# LED_Triangle.net
KiCad netlist of a schematic drawn in EAGLE
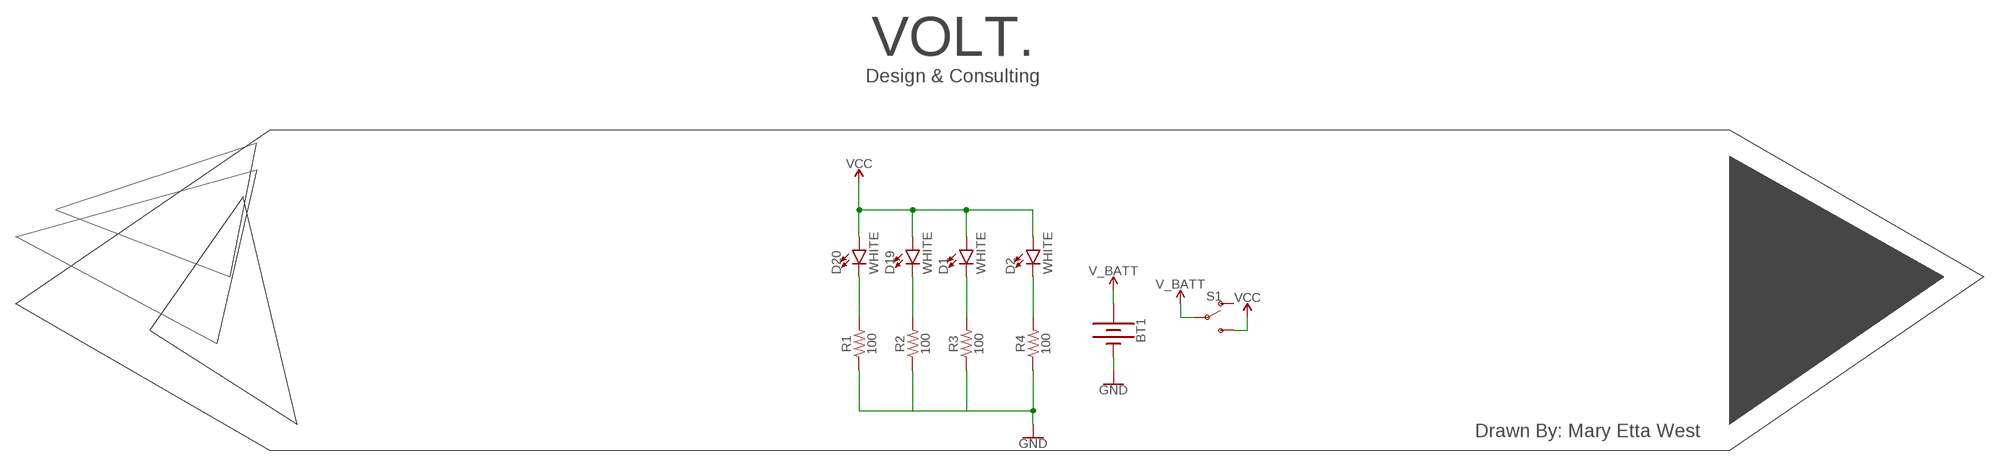
[diagram p0: schematic, sheet 1]

(export (version "E")
  (design (tool "Eeschema 10.0.6"))
  (components
    (comp (ref "BT1")
      (value "BATTERY-12MM_SMD")
      (footprint "eagle-import:BATTCON_12MM")
      (libsource (lib "eagle-import") (part "BATTERY-12MM_SMD"))
    )
    (comp (ref "D1")
      (value "WHITE")
      (footprint "eagle-import:LED-1206")
      (libsource (lib "eagle-import") (part "LED-WHITE1206"))
    )
    (comp (ref "D2")
      (value "WHITE")
      (footprint "eagle-import:LED-1206")
      (libsource (lib "eagle-import") (part "LED-WHITE1206"))
    )
    (comp (ref "D19")
      (value "WHITE")
      (footprint "eagle-import:LED-1206")
      (libsource (lib "eagle-import") (part "LED-WHITE1206"))
    )
    (comp (ref "D20")
      (value "WHITE")
      (footprint "eagle-import:LED-1206")
      (libsource (lib "eagle-import") (part "LED-WHITE1206"))
    )
    (comp (ref "R1")
      (value "100")
      (footprint "eagle-import:0603")
      (libsource (lib "eagle-import") (part "100OHM-0603-1/4W-5%"))
    )
    (comp (ref "R2")
      (value "100")
      (footprint "eagle-import:0603")
      (libsource (lib "eagle-import") (part "100OHM-0603-1/4W-5%"))
    )
    (comp (ref "R3")
      (value "100")
      (footprint "eagle-import:0603")
      (libsource (lib "eagle-import") (part "100OHM-0603-1/4W-5%"))
    )
    (comp (ref "R4")
      (value "100")
      (footprint "eagle-import:0603")
      (libsource (lib "eagle-import") (part "100OHM-0603-1/4W-5%"))
    )
    (comp (ref "S1")
      (value "SWITCH-SPDT-SMD-RIGHT-ANGLE")
      (footprint "eagle-import:SWITCH_SPST_SMD_A")
      (libsource (lib "eagle-import") (part "SWITCH-SPDT-SMD-RIGHT-ANGLE"))
    )
  )
  (nets
    (net (code "1") (name "GND") (class "Default")
      (node (ref "BT1") (pin "GND") (pinfunction "-_GND") (pintype "power_in"))
      (node (ref "R1") (pin "1") (pinfunction "1_1") (pintype "passive"))
      (node (ref "R2") (pin "1") (pinfunction "1_1") (pintype "passive"))
      (node (ref "R3") (pin "1") (pinfunction "1_1") (pintype "passive"))
      (node (ref "R4") (pin "1") (pinfunction "1_1") (pintype "passive"))
    )
    (net (code "2") (name "Net-(D1-PadC)") (class "Default")
      (node (ref "D1") (pin "C") (pinfunction "C_C") (pintype "passive"))
      (node (ref "R3") (pin "2") (pinfunction "2_2") (pintype "passive"))
    )
    (net (code "3") (name "Net-(D2-PadC)") (class "Default")
      (node (ref "D2") (pin "C") (pinfunction "C_C") (pintype "passive"))
      (node (ref "R4") (pin "2") (pinfunction "2_2") (pintype "passive"))
    )
    (net (code "4") (name "Net-(D19-PadC)") (class "Default")
      (node (ref "D19") (pin "C") (pinfunction "C_C") (pintype "passive"))
      (node (ref "R2") (pin "2") (pinfunction "2_2") (pintype "passive"))
    )
    (net (code "5") (name "Net-(D20-PadC)") (class "Default")
      (node (ref "D20") (pin "C") (pinfunction "C_C") (pintype "passive"))
      (node (ref "R1") (pin "2") (pinfunction "2_2") (pintype "passive"))
    )
    (net (code "6") (name "VCC") (class "Default")
      (node (ref "D1") (pin "A") (pinfunction "A_A") (pintype "passive"))
      (node (ref "D19") (pin "A") (pinfunction "A_A") (pintype "passive"))
      (node (ref "D2") (pin "A") (pinfunction "A_A") (pintype "passive"))
      (node (ref "D20") (pin "A") (pinfunction "A_A") (pintype "passive"))
      (node (ref "S1") (pin "3") (pinfunction "S_3") (pintype "passive"))
    )
    (net (code "7") (name "V_BATT") (class "Default")
      (node (ref "BT1") (pin "PWR@1") (pinfunction "+_PWR@1") (pintype "power_in"))
      (node (ref "S1") (pin "2") (pinfunction "P_2") (pintype "passive"))
    )
    (net (code "8") (name "unconnected-(S1-O-Pad1)") (class "Default")
      (node (ref "S1") (pin "1") (pinfunction "O_1") (pintype "passive"))
    )
  )
)
